# mk312lite_V4.net
KiCad netlist of a schematic drawn in EAGLE
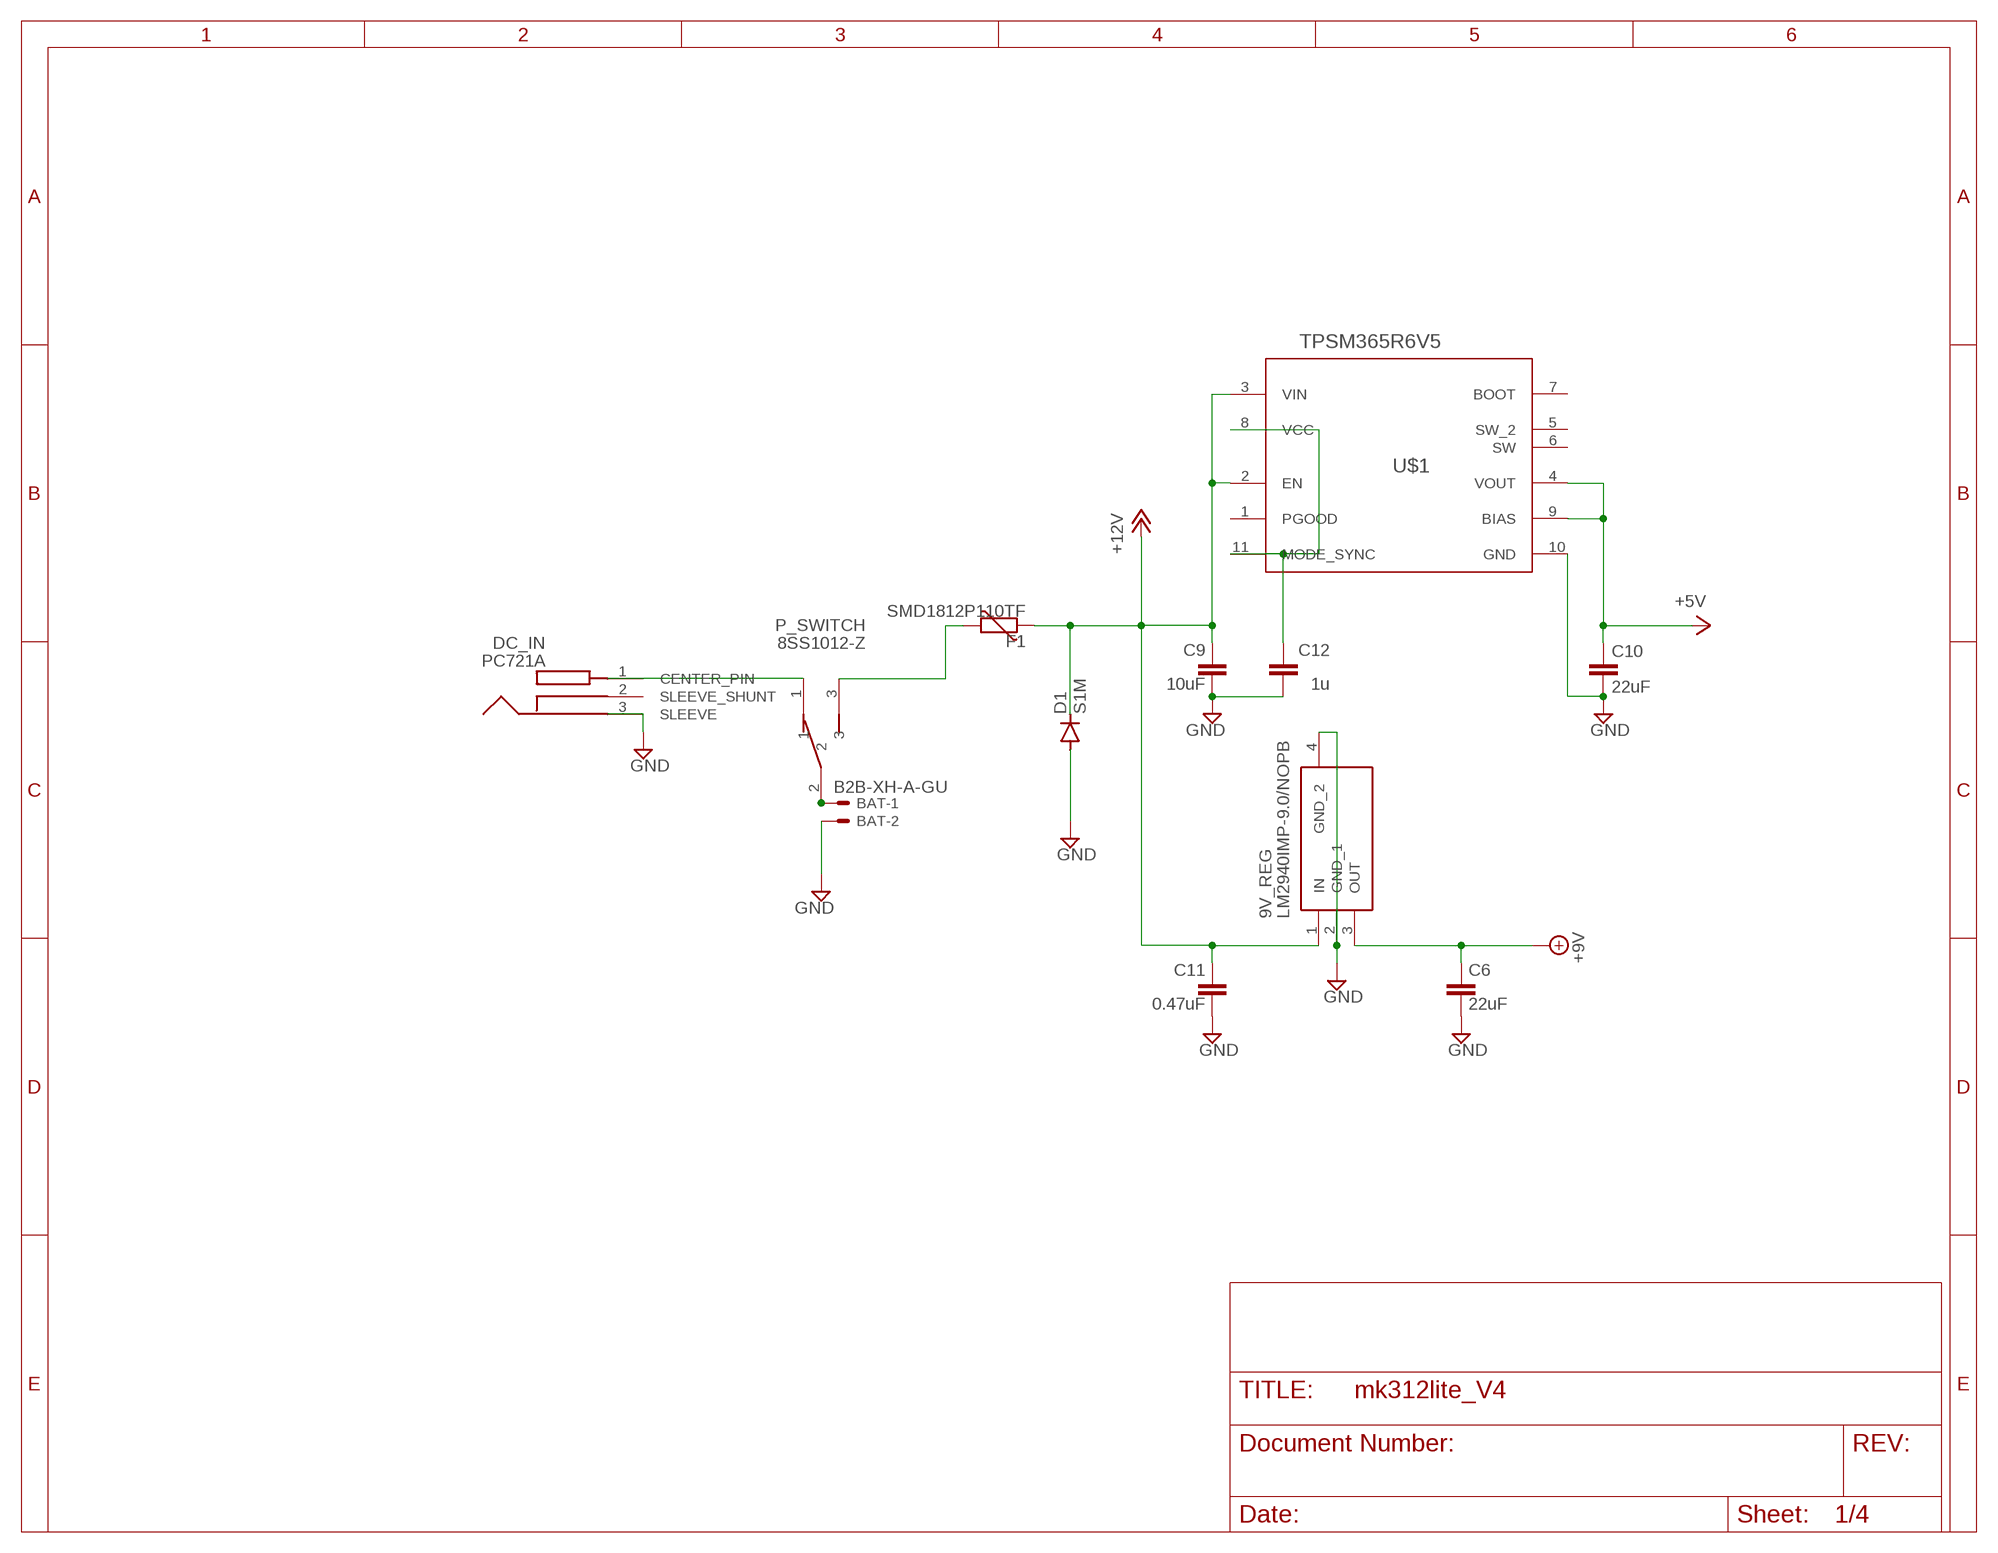
[diagram p0: schematic, sheet 1]
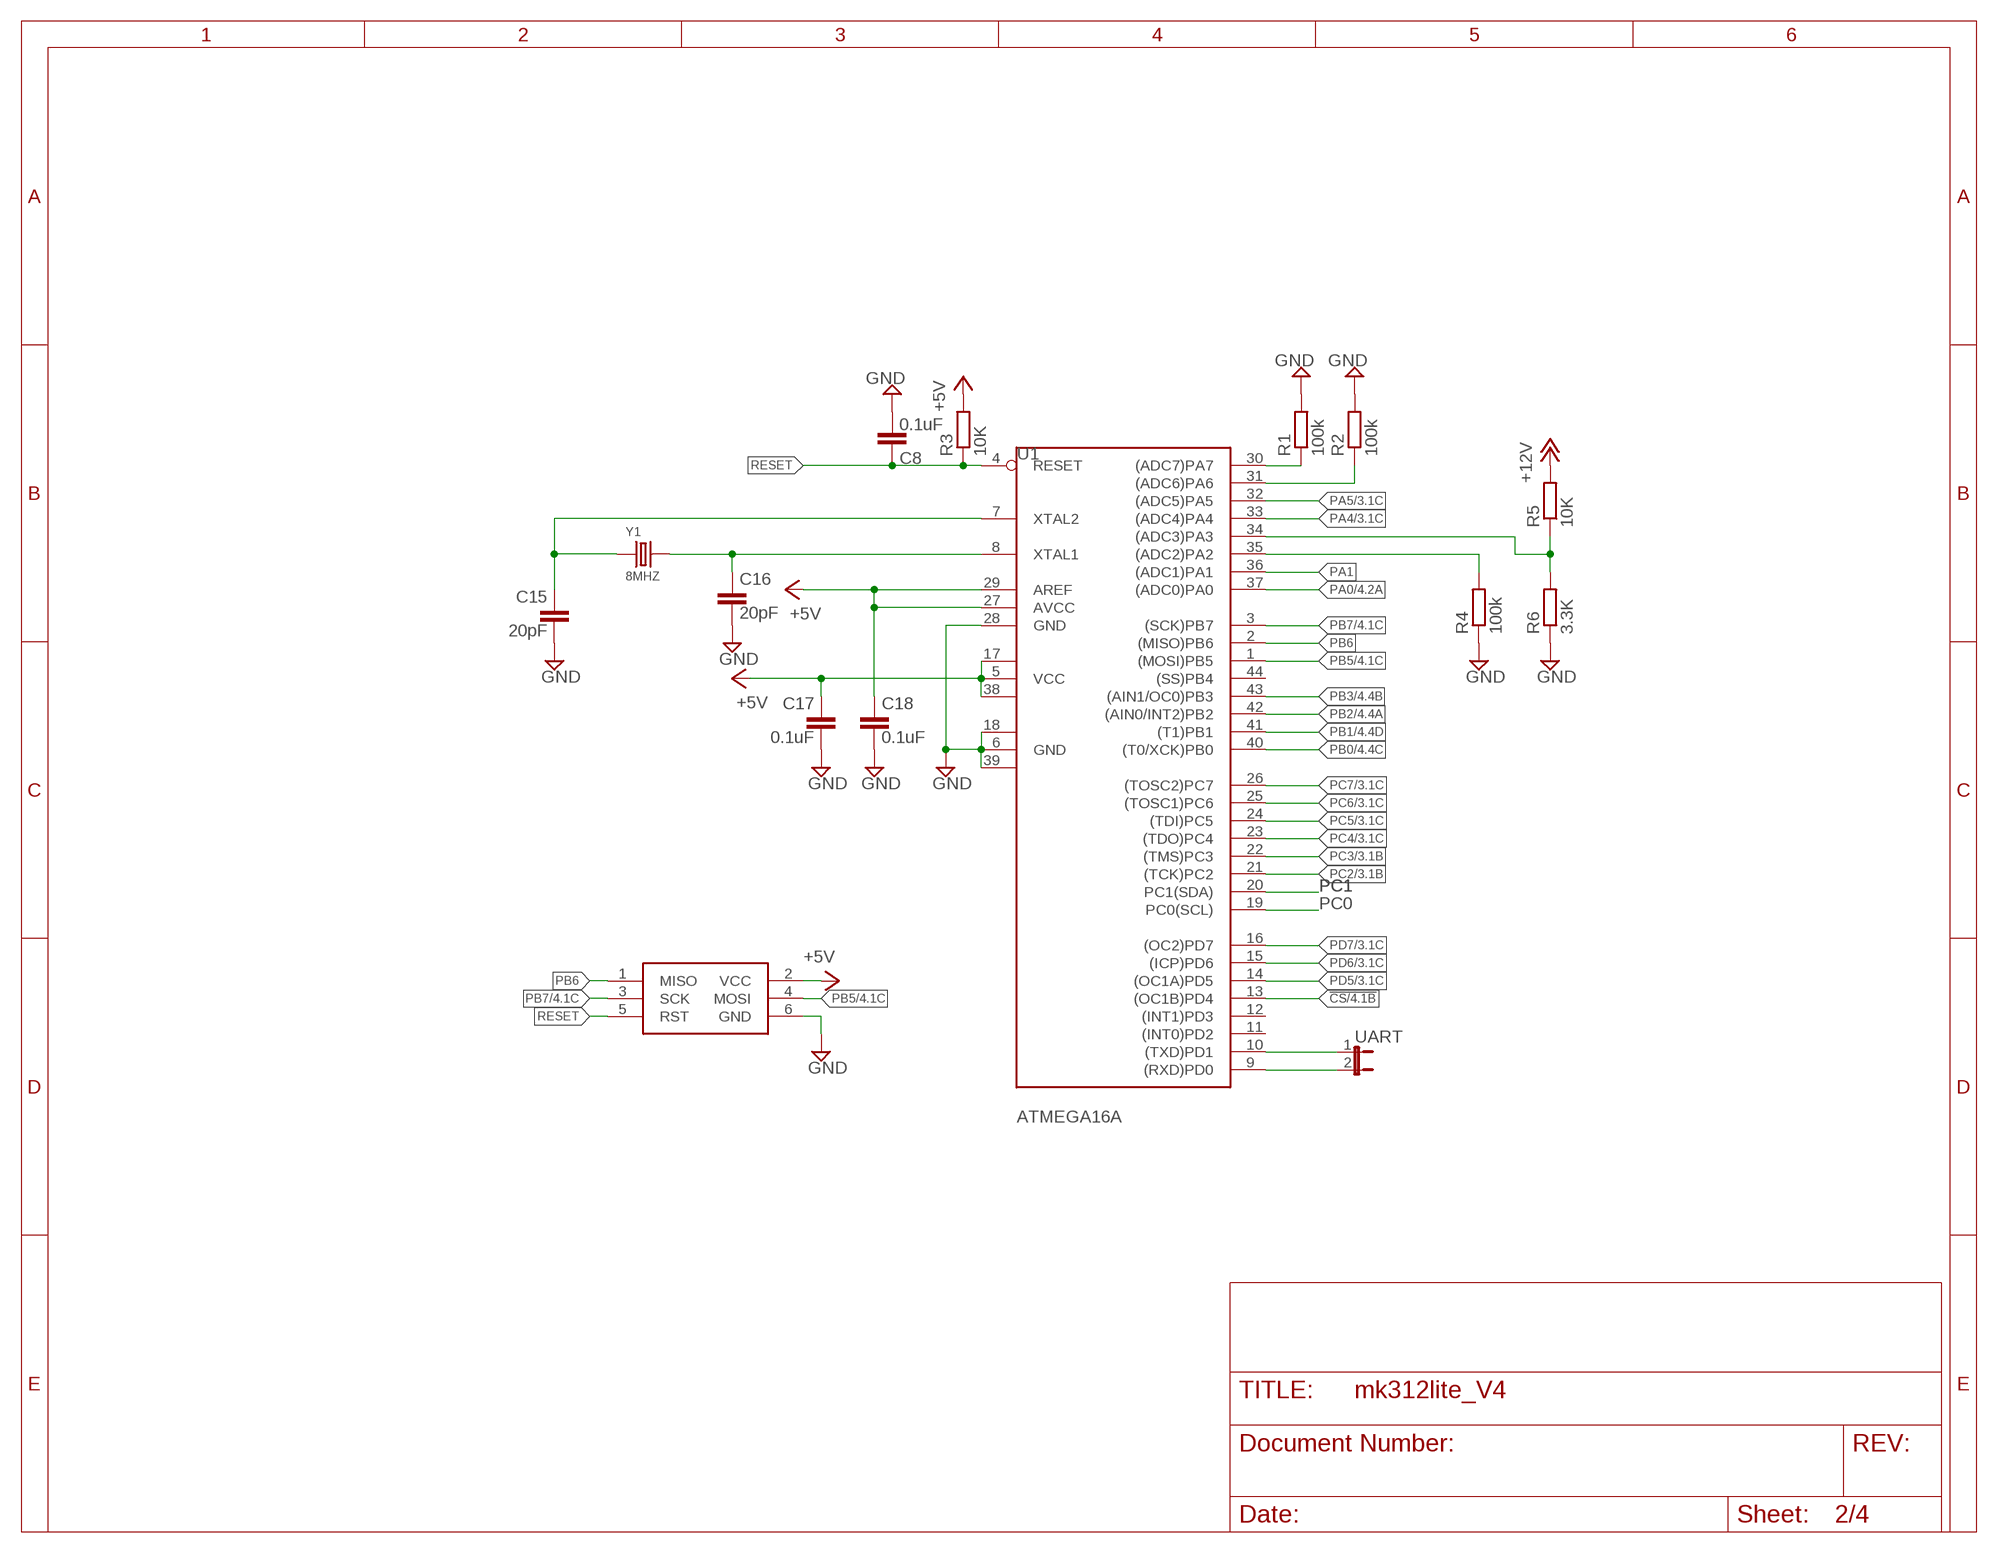
[diagram p1: schematic, sheet 2]
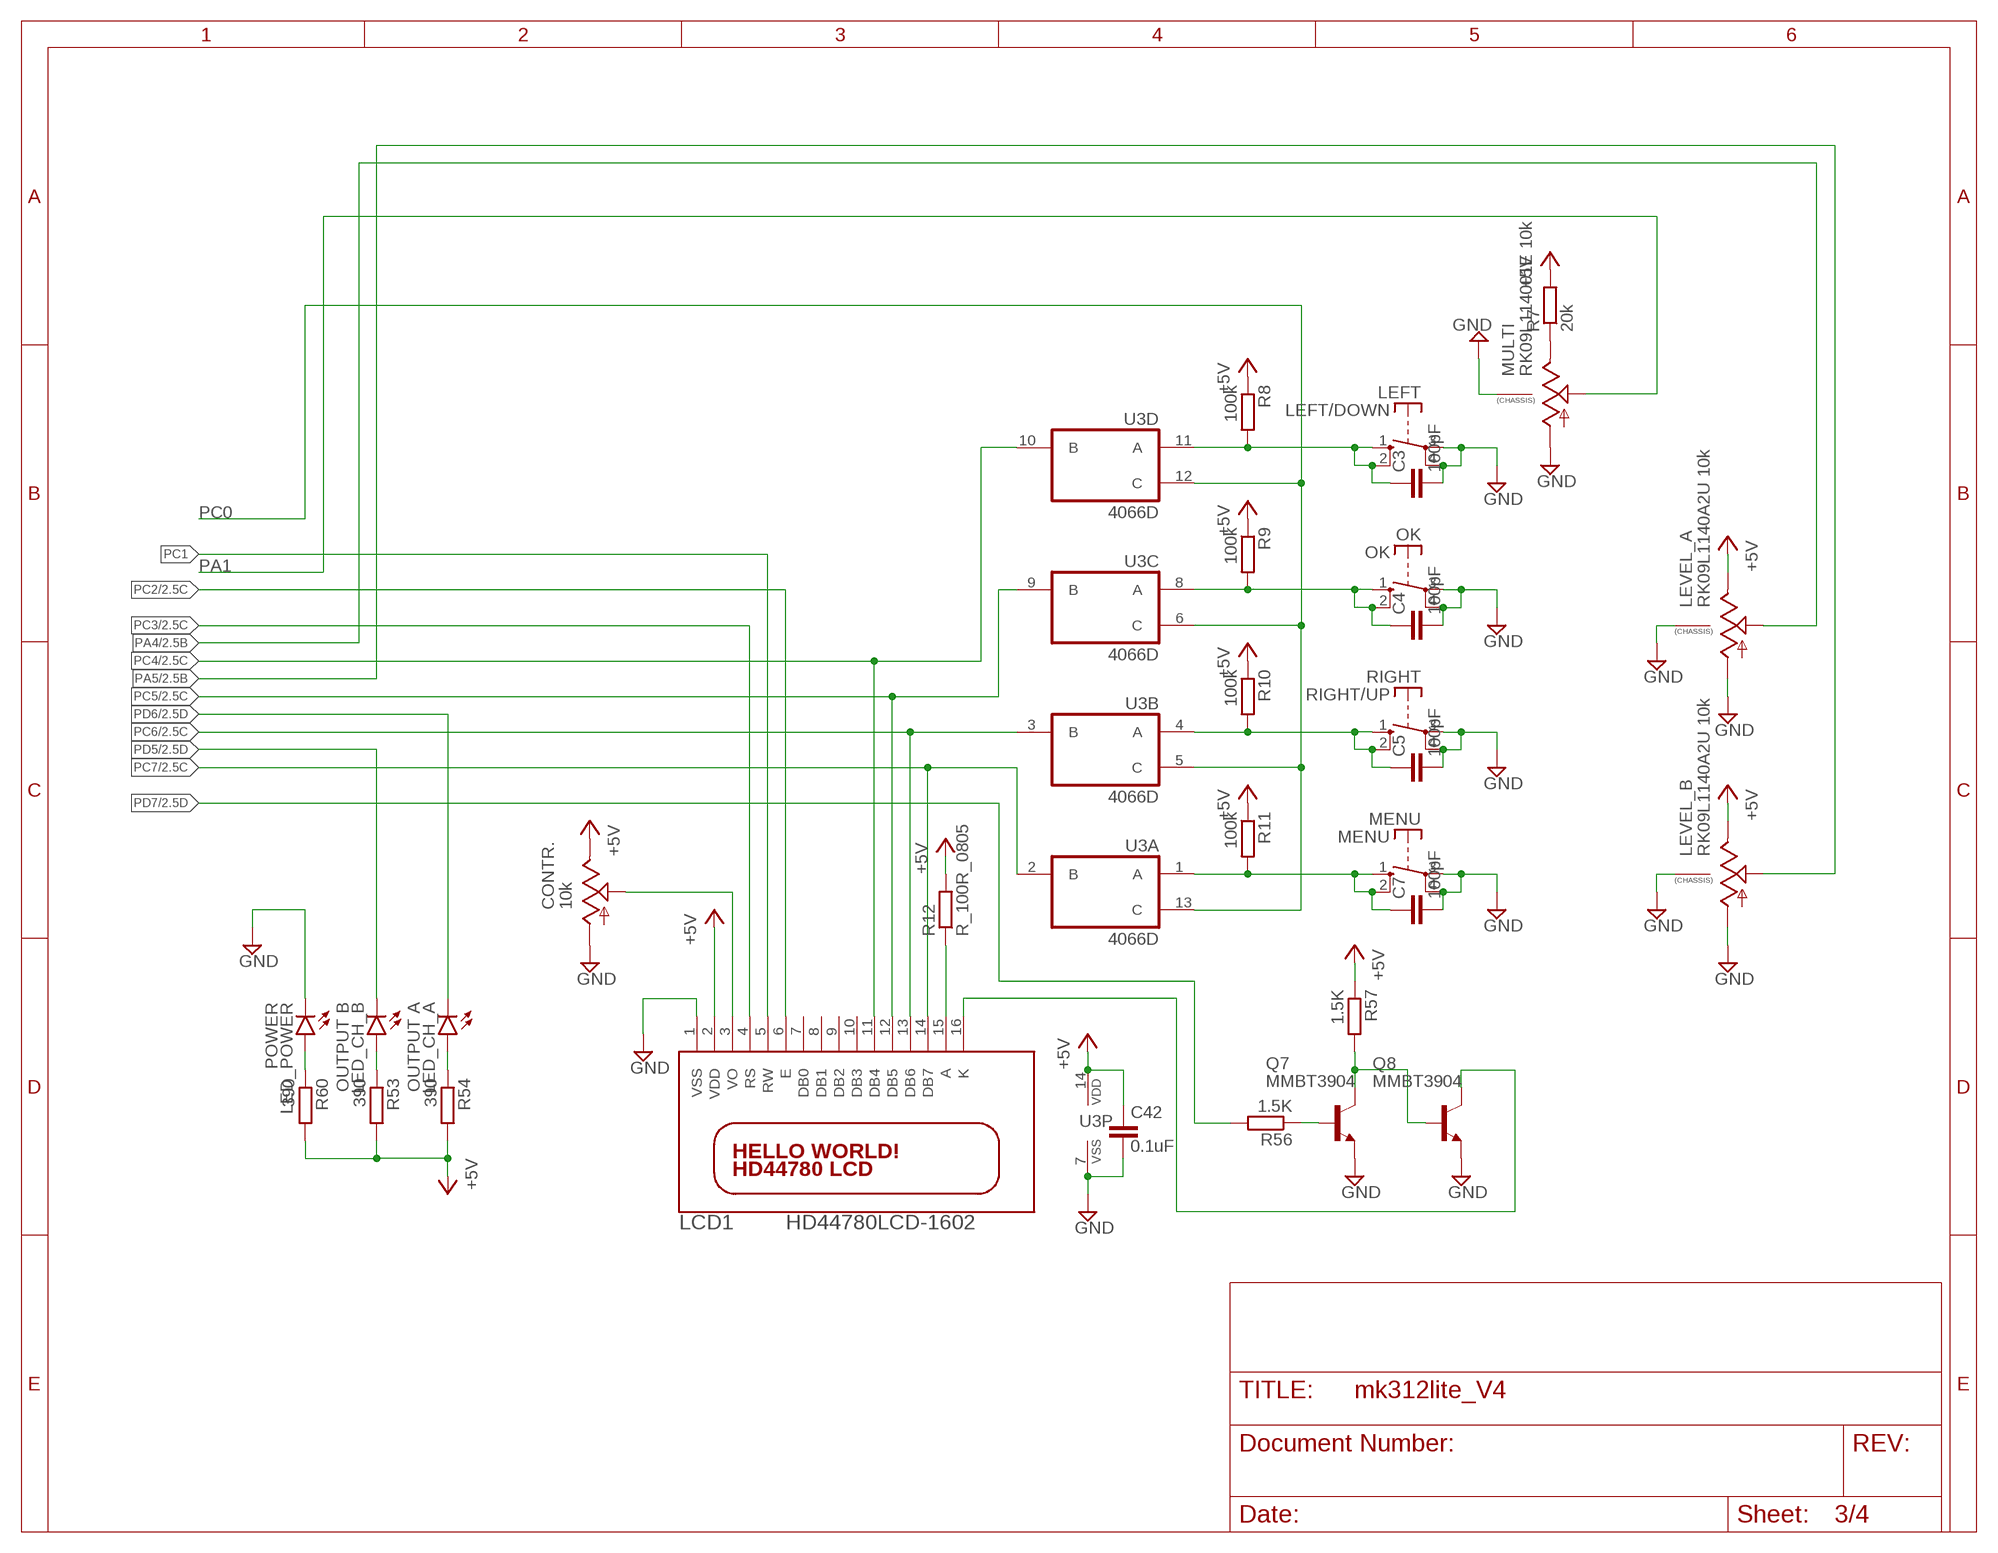
[diagram p2: schematic, sheet 3]
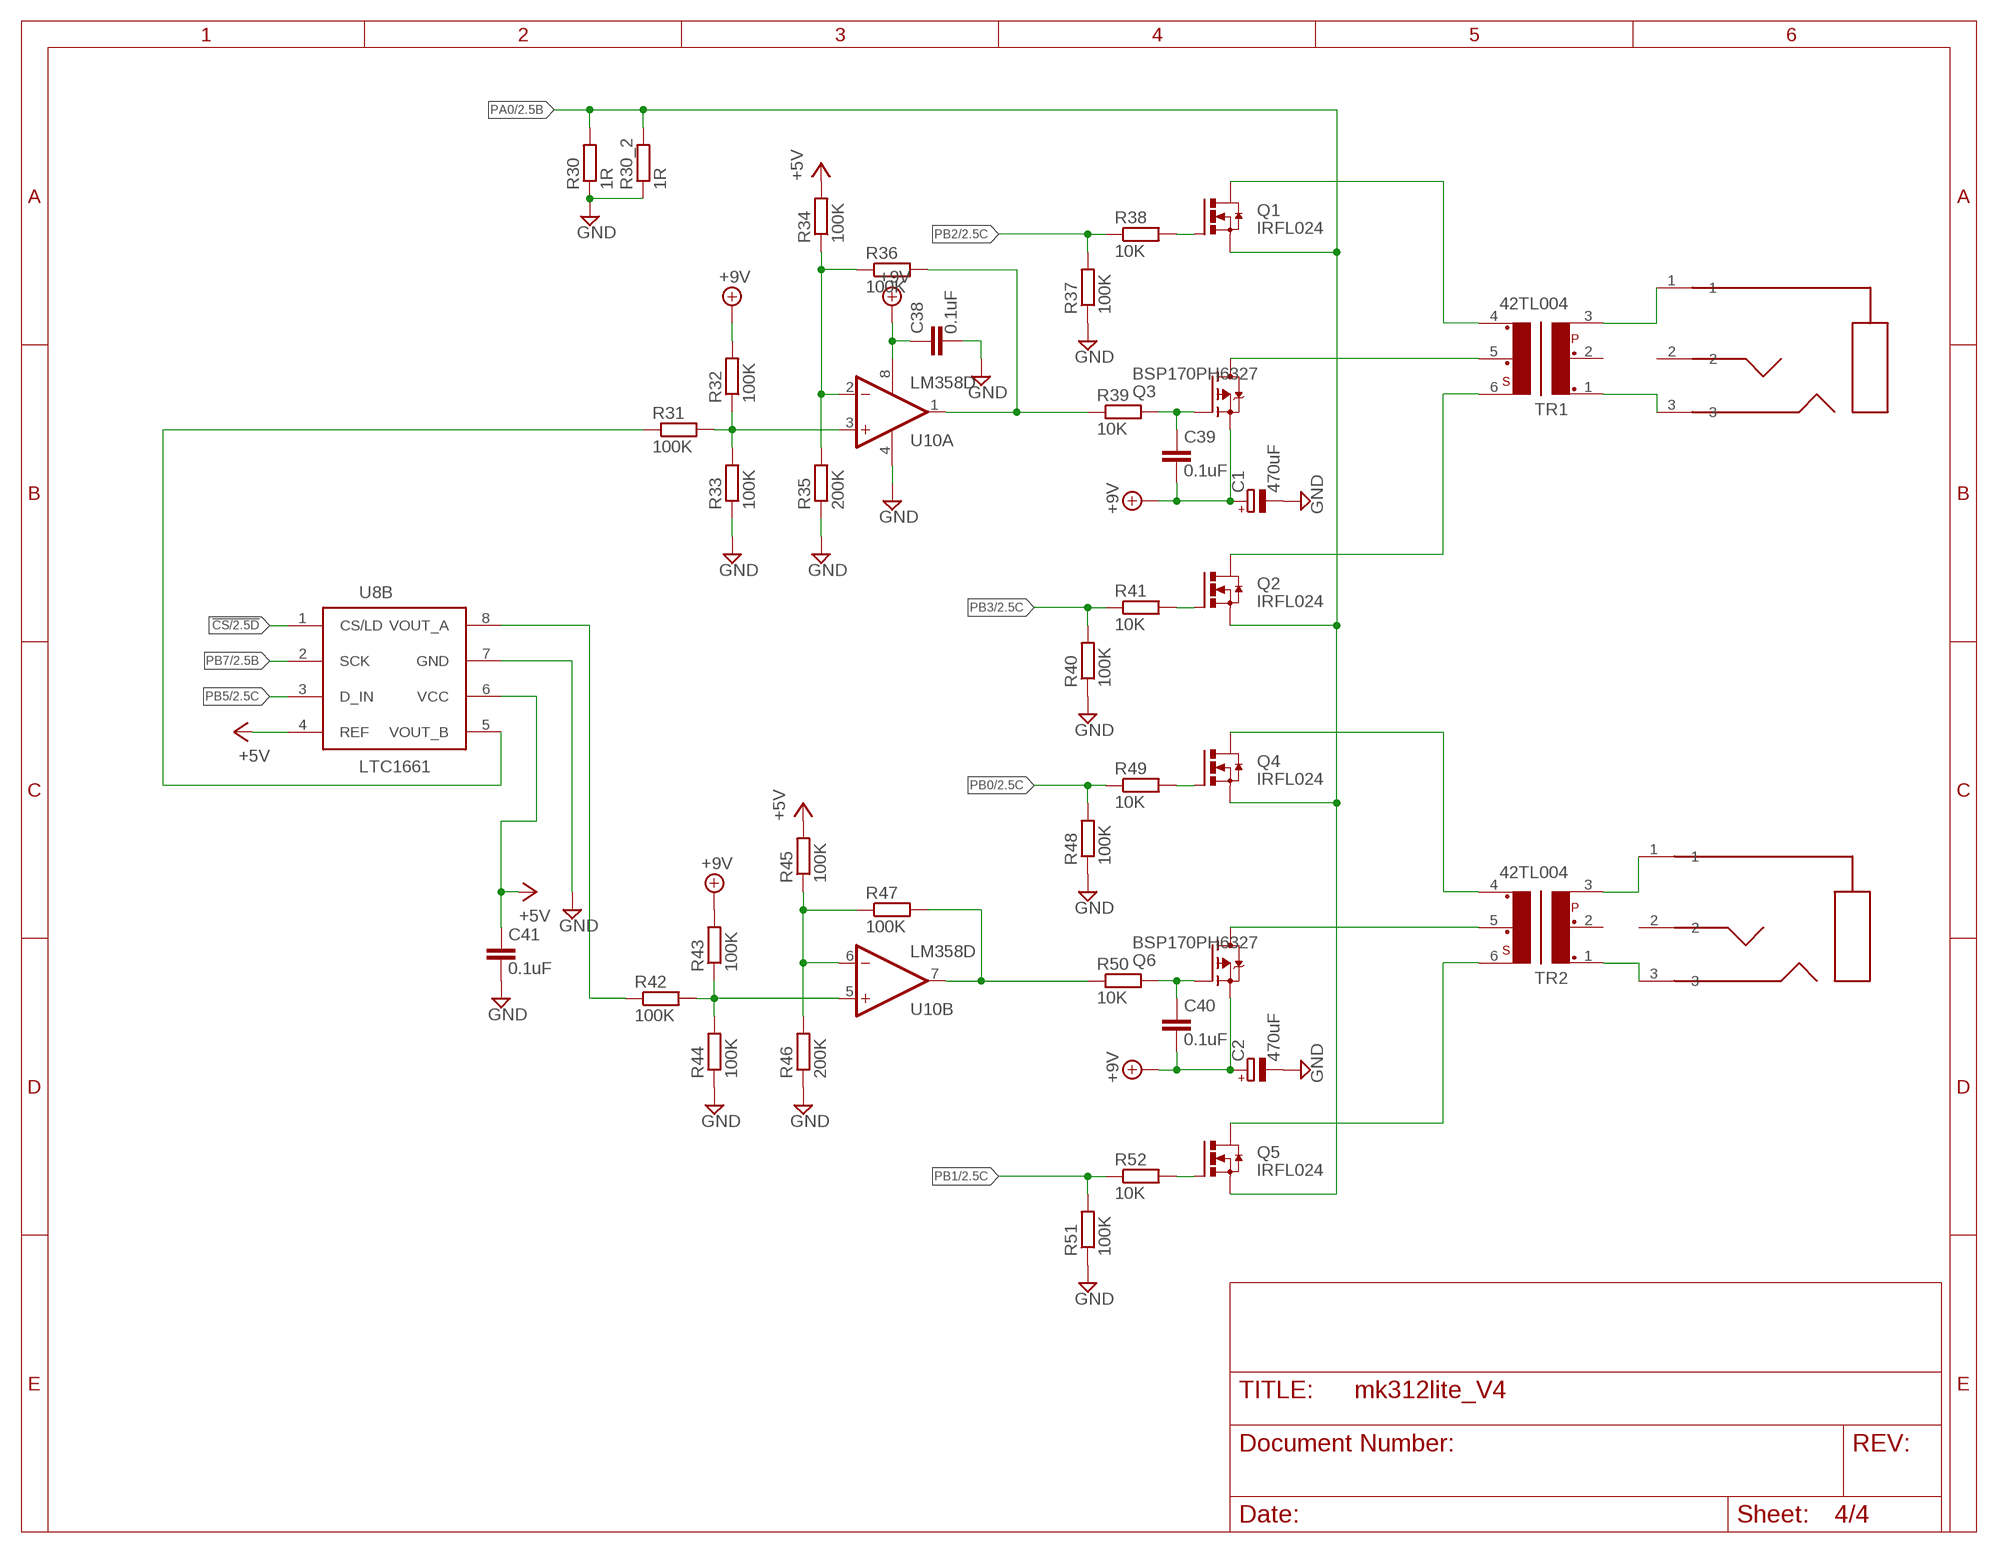
[diagram p3: schematic, sheet 4]

(export (version "E")
  (design (tool "Eeschema 10.0.6"))
  (components
    (comp (ref "C3")
      (value "100pF")
      (footprint "eagle-import:C0805")
      (libsource (lib "eagle-import") (part "C-EUC0805"))
    )
    (comp (ref "C4")
      (value "100pF")
      (footprint "eagle-import:C0805")
      (libsource (lib "eagle-import") (part "C-EUC0805"))
    )
    (comp (ref "C5")
      (value "100pF")
      (footprint "eagle-import:C0805")
      (libsource (lib "eagle-import") (part "C-EUC0805"))
    )
    (comp (ref "C7")
      (value "100pF")
      (footprint "eagle-import:C0805")
      (libsource (lib "eagle-import") (part "C-EUC0805"))
    )
    (comp (ref "C42")
      (value "0.1uF")
      (footprint "eagle-import:C0805")
      (libsource (lib "eagle-import") (part "C-EUC0805"))
    )
    (comp (ref "CONTR.")
      (value "10k")
      (footprint "eagle-import:B25P")
      (libsource (lib "eagle-import") (part "TRIM_US-B25P"))
    )
    (comp (ref "LCD1")
      (value "HD44780LCD-1602")
      (footprint "eagle-import:LCD1602")
      (libsource (lib "eagle-import") (part "HD44780LCD-1602"))
    )
    (comp (ref "LED_CH_A")
      (value "OUTPUT A")
      (footprint "eagle-import:LED3MM")
      (libsource (lib "eagle-import") (part "LED3MM"))
    )
    (comp (ref "LED_CH_B")
      (value "OUTPUT B")
      (footprint "eagle-import:LED3MM")
      (libsource (lib "eagle-import") (part "LED3MM"))
    )
    (comp (ref "LED_POWER")
      (value "POWER")
      (footprint "eagle-import:LED3MM")
      (libsource (lib "eagle-import") (part "LED3MM"))
    )
    (comp (ref "LEFT")
      (value "LEFT/DOWN")
      (footprint "eagle-import:DTE6K")
      (libsource (lib "eagle-import") (part "DTE6K"))
    )
    (comp (ref "LEVEL_A")
      (value "RK09L1140A2U 10k")
      (footprint "eagle-import:9MM_SNAP-IN_POT")
      (libsource (lib "eagle-import") (part "9MM_SNAP-IN_POT_CHASSIS"))
    )
    (comp (ref "LEVEL_B")
      (value "RK09L1140A2U 10k")
      (footprint "eagle-import:9MM_SNAP-IN_POT")
      (libsource (lib "eagle-import") (part "9MM_SNAP-IN_POT_CHASSIS"))
    )
    (comp (ref "MENU")
      (value "MENU")
      (footprint "eagle-import:DTE6K")
      (libsource (lib "eagle-import") (part "DTE6K"))
    )
    (comp (ref "MULTI")
      (value "RK09L114001E 10k")
      (footprint "eagle-import:9MM_SNAP-IN_POT")
      (libsource (lib "eagle-import") (part "9MM_SNAP-IN_POT_CHASSIS"))
    )
    (comp (ref "OK")
      (value "OK")
      (footprint "eagle-import:DTE6K")
      (libsource (lib "eagle-import") (part "DTE6K"))
    )
    (comp (ref "Q7")
      (value "MMBT3904")
      (footprint "eagle-import:SOT23-BEC")
      (libsource (lib "eagle-import") (part "-NPN-SOT23-BECMMBT3904LT1"))
    )
    (comp (ref "Q8")
      (value "MMBT3904")
      (footprint "eagle-import:SOT23-BEC")
      (libsource (lib "eagle-import") (part "-NPN-SOT23-BECMMBT3904LT1"))
    )
    (comp (ref "R7")
      (value "20k")
      (footprint "eagle-import:R0805")
      (libsource (lib "eagle-import") (part "R-EU_R0805"))
    )
    (comp (ref "R8")
      (value "100k")
      (footprint "eagle-import:R0805")
      (libsource (lib "eagle-import") (part "R-EU_R0805"))
    )
    (comp (ref "R9")
      (value "100k")
      (footprint "eagle-import:R0805")
      (libsource (lib "eagle-import") (part "R-EU_R0805"))
    )
    (comp (ref "R10")
      (value "100k")
      (footprint "eagle-import:R0805")
      (libsource (lib "eagle-import") (part "R-EU_R0805"))
    )
    (comp (ref "R11")
      (value "100k")
      (footprint "eagle-import:R0805")
      (libsource (lib "eagle-import") (part "R-EU_R0805"))
    )
    (comp (ref "R12")
      (value "R_100R_0805")
      (footprint "eagle-import:R0805")
      (fields (field (name "LCSC_PART") "C17408"))
      (libsource (lib "eagle-import") (part "R__0805100R"))
    )
    (comp (ref "R53")
      (value "390")
      (footprint "eagle-import:R0805")
      (libsource (lib "eagle-import") (part "R-EU_R0805"))
    )
    (comp (ref "R54")
      (value "390")
      (footprint "eagle-import:R0805")
      (libsource (lib "eagle-import") (part "R-EU_R0805"))
    )
    (comp (ref "R56")
      (value "1.5K")
      (footprint "eagle-import:R0805")
      (libsource (lib "eagle-import") (part "R-EU_R0805"))
    )
    (comp (ref "R57")
      (value "1.5K")
      (footprint "eagle-import:R0805")
      (libsource (lib "eagle-import") (part "R-EU_R0805"))
    )
    (comp (ref "R60")
      (value "390")
      (footprint "eagle-import:R0805")
      (libsource (lib "eagle-import") (part "R-EU_R0805"))
    )
    (comp (ref "RIGHT")
      (value "RIGHT/UP")
      (footprint "eagle-import:DTE6K")
      (libsource (lib "eagle-import") (part "DTE6K"))
    )
    (comp (ref "U3")
      (value "4066D")
      (footprint "eagle-import:SO14")
      (libsource (lib "eagle-import") (part "4066D"))
    )
    (comp (ref "C8")
      (value "0.1uF")
      (footprint "eagle-import:C0805")
      (libsource (lib "eagle-import") (part "C-EUC0805"))
    )
    (comp (ref "C15")
      (value "20pF")
      (footprint "eagle-import:C0603")
      (libsource (lib "eagle-import") (part "C-EUC0603"))
    )
    (comp (ref "C16")
      (value "20pF")
      (footprint "eagle-import:C0603")
      (libsource (lib "eagle-import") (part "C-EUC0603"))
    )
    (comp (ref "C17")
      (value "0.1uF")
      (footprint "eagle-import:C0805")
      (libsource (lib "eagle-import") (part "C-EUC0805"))
    )
    (comp (ref "C18")
      (value "0.1uF")
      (footprint "eagle-import:C0805")
      (libsource (lib "eagle-import") (part "C-EUC0805"))
    )
    (comp (ref "ISP1")
      (value "AVRISP-6")
      (footprint "eagle-import:AVRISP")
      (libsource (lib "eagle-import") (part "AVRISP-6"))
    )
    (comp (ref "R1")
      (value "100k")
      (footprint "eagle-import:R0805")
      (libsource (lib "eagle-import") (part "R-EU_R0805"))
    )
    (comp (ref "R2")
      (value "100k")
      (footprint "eagle-import:R0805")
      (libsource (lib "eagle-import") (part "R-EU_R0805"))
    )
    (comp (ref "R3")
      (value "10K")
      (footprint "eagle-import:R0805")
      (libsource (lib "eagle-import") (part "R-EU_R0805"))
    )
    (comp (ref "R4")
      (value "100k")
      (footprint "eagle-import:R0805")
      (libsource (lib "eagle-import") (part "R-EU_R0805"))
    )
    (comp (ref "R5")
      (value "10K")
      (footprint "eagle-import:R0805")
      (libsource (lib "eagle-import") (part "R-EU_R0805"))
    )
    (comp (ref "R6")
      (value "3.3K")
      (footprint "eagle-import:R0805")
      (libsource (lib "eagle-import") (part "R-EU_R0805"))
    )
    (comp (ref "U1")
      (value "ATMEGA16A")
      (footprint "eagle-import:TQFP44")
      (fields (field (name "MPN") "ATMEGA16-16AU"))
      (libsource (lib "eagle-import") (part "MEGA16-A"))
    )
    (comp (ref "UART")
      (value "JP1E")
      (footprint "eagle-import:JP1")
      (libsource (lib "eagle-import") (part "JP1E"))
    )
    (comp (ref "Y1")
      (value "8MHZ")
      (footprint "eagle-import:X2-SMD-5.0X3.2X1.3MM")
      (fields (field (name "MPN") "5032/2P"))
      (libsource (lib "eagle-import") (part "SMD-CRYSTAL-8MHZ-20PF-20PPM(2P-5.0X3.2MM)"))
    )
    (comp (ref "C1")
      (value "470uF")
      (footprint "eagle-import:150CLZ-1010")
      (libsource (lib "eagle-import") (part "CPOL-EU150CLZ-1010"))
    )
    (comp (ref "C2")
      (value "470uF")
      (footprint "eagle-import:150CLZ-1010")
      (libsource (lib "eagle-import") (part "CPOL-EU150CLZ-1010"))
    )
    (comp (ref "C38")
      (value "0.1uF")
      (footprint "eagle-import:C0805")
      (libsource (lib "eagle-import") (part "C-EUC0805"))
    )
    (comp (ref "C39")
      (value "0.1uF")
      (footprint "eagle-import:C0805")
      (libsource (lib "eagle-import") (part "C-EUC0805"))
    )
    (comp (ref "C40")
      (value "0.1uF")
      (footprint "eagle-import:C0805")
      (libsource (lib "eagle-import") (part "C-EUC0805"))
    )
    (comp (ref "C41")
      (value "0.1uF")
      (footprint "eagle-import:C0805")
      (libsource (lib "eagle-import") (part "C-EUC0805"))
    )
    (comp (ref "CHAN_A")
      (value "PJ-301C")
      (footprint "eagle-import:PJ-301C")
      (libsource (lib "eagle-import") (part "PC-301C"))
    )
    (comp (ref "CHAN_B")
      (value "PJ-301C")
      (footprint "eagle-import:PJ-301C")
      (libsource (lib "eagle-import") (part "PC-301C"))
    )
    (comp (ref "Q1")
      (value "IRFL024")
      (footprint "eagle-import:SOT223")
      (libsource (lib "eagle-import") (part "N-HEXFET-2D_?-SOT232IRLL2705"))
    )
    (comp (ref "Q2")
      (value "IRFL024")
      (footprint "eagle-import:SOT223")
      (libsource (lib "eagle-import") (part "N-HEXFET-2D_?-SOT232IRLL2705"))
    )
    (comp (ref "Q3")
      (value "BSP170PH6327")
      (footprint "eagle-import:SOT230P700X180-4N")
      (libsource (lib "eagle-import") (part "IRFL9014TRPBF"))
    )
    (comp (ref "Q4")
      (value "IRFL024")
      (footprint "eagle-import:SOT223")
      (libsource (lib "eagle-import") (part "N-HEXFET-2D_?-SOT232IRLL2705"))
    )
    (comp (ref "Q5")
      (value "IRFL024")
      (footprint "eagle-import:SOT223")
      (libsource (lib "eagle-import") (part "N-HEXFET-2D_?-SOT232IRLL2705"))
    )
    (comp (ref "Q6")
      (value "BSP170PH6327")
      (footprint "eagle-import:SOT230P700X180-4N")
      (libsource (lib "eagle-import") (part "IRFL9014TRPBF"))
    )
    (comp (ref "R30")
      (value "1R")
      (footprint "eagle-import:R1206")
      (libsource (lib "eagle-import") (part "R-EU_R1206"))
    )
    (comp (ref "R30_2")
      (value "1R")
      (footprint "eagle-import:R1206")
      (libsource (lib "eagle-import") (part "R-EU_R1206"))
    )
    (comp (ref "R31")
      (value "100K")
      (footprint "eagle-import:R0805")
      (libsource (lib "eagle-import") (part "R-EU_R0805"))
    )
    (comp (ref "R32")
      (value "100K")
      (footprint "eagle-import:R0805")
      (libsource (lib "eagle-import") (part "R-EU_R0805"))
    )
    (comp (ref "R33")
      (value "100K")
      (footprint "eagle-import:R0805")
      (libsource (lib "eagle-import") (part "R-EU_R0805"))
    )
    (comp (ref "R34")
      (value "100K")
      (footprint "eagle-import:R0805")
      (libsource (lib "eagle-import") (part "R-EU_R0805"))
    )
    (comp (ref "R35")
      (value "200K")
      (footprint "eagle-import:R0805")
      (libsource (lib "eagle-import") (part "R-EU_R0805"))
    )
    (comp (ref "R36")
      (value "100K")
      (footprint "eagle-import:R0805")
      (libsource (lib "eagle-import") (part "R-EU_R0805"))
    )
    (comp (ref "R37")
      (value "100K")
      (footprint "eagle-import:R0805")
      (libsource (lib "eagle-import") (part "R-EU_R0805"))
    )
    (comp (ref "R38")
      (value "10K")
      (footprint "eagle-import:R0805")
      (libsource (lib "eagle-import") (part "R-EU_R0805"))
    )
    (comp (ref "R39")
      (value "10K")
      (footprint "eagle-import:R0805")
      (libsource (lib "eagle-import") (part "R-EU_R0805"))
    )
    (comp (ref "R40")
      (value "100K")
      (footprint "eagle-import:R0805")
      (libsource (lib "eagle-import") (part "R-EU_R0805"))
    )
    (comp (ref "R41")
      (value "10K")
      (footprint "eagle-import:R0805")
      (libsource (lib "eagle-import") (part "R-EU_R0805"))
    )
    (comp (ref "R42")
      (value "100K")
      (footprint "eagle-import:R0805")
      (libsource (lib "eagle-import") (part "R-EU_R0805"))
    )
    (comp (ref "R43")
      (value "100K")
      (footprint "eagle-import:R0805")
      (libsource (lib "eagle-import") (part "R-EU_R0805"))
    )
    (comp (ref "R44")
      (value "100K")
      (footprint "eagle-import:R0805")
      (libsource (lib "eagle-import") (part "R-EU_R0805"))
    )
    (comp (ref "R45")
      (value "100K")
      (footprint "eagle-import:R0805")
      (libsource (lib "eagle-import") (part "R-EU_R0805"))
    )
    (comp (ref "R46")
      (value "200K")
      (footprint "eagle-import:R0805")
      (libsource (lib "eagle-import") (part "R-EU_R0805"))
    )
    (comp (ref "R47")
      (value "100K")
      (footprint "eagle-import:R0805")
      (libsource (lib "eagle-import") (part "R-EU_R0805"))
    )
    (comp (ref "R48")
      (value "100K")
      (footprint "eagle-import:R0805")
      (libsource (lib "eagle-import") (part "R-EU_R0805"))
    )
    (comp (ref "R49")
      (value "10K")
      (footprint "eagle-import:R0805")
      (libsource (lib "eagle-import") (part "R-EU_R0805"))
    )
    (comp (ref "R50")
      (value "10K")
      (footprint "eagle-import:R0805")
      (libsource (lib "eagle-import") (part "R-EU_R0805"))
    )
    (comp (ref "R51")
      (value "100K")
      (footprint "eagle-import:R0805")
      (libsource (lib "eagle-import") (part "R-EU_R0805"))
    )
    (comp (ref "R52")
      (value "10K")
      (footprint "eagle-import:R0805")
      (libsource (lib "eagle-import") (part "R-EU_R0805"))
    )
    (comp (ref "TR1")
      (value "42TL004")
      (footprint "eagle-import:42TL")
      (libsource (lib "eagle-import") (part "42T?L023"))
    )
    (comp (ref "TR2")
      (value "42TL004")
      (footprint "eagle-import:42TL")
      (libsource (lib "eagle-import") (part "42T?L023"))
    )
    (comp (ref "U8B")
      (value "LTC1661")
      (footprint "eagle-import:MSOP8")
      (libsource (lib "eagle-import") (part "LTC1661IMS8"))
    )
    (comp (ref "U10")
      (value "LM358D")
      (footprint "eagle-import:SO08")
      (libsource (lib "eagle-import") (part "LM358D"))
    )
    (comp (ref "9V_REG")
      (value "LM2940IMP-9.0/NOPB")
      (footprint "eagle-import:SOT230P700X180-4N")
      (fields (field (name "MOUSER_PART_NUMBER") "926-LM2940IMP90NOPB"))
      (libsource (lib "eagle-import") (part "LM2940IMP-9.0_NOPB"))
    )
    (comp (ref "BAT")
      (value "B2B-XH-A-GU")
      (footprint "eagle-import:JST-XH-02-PACKAGE-LONG-PAD")
      (libsource (lib "eagle-import") (part "JST-XH-02-PIN-LONG-PAD"))
    )
    (comp (ref "C6")
      (value "22uF")
      (footprint "eagle-import:C1206")
      (libsource (lib "eagle-import") (part "C-EUC1206"))
    )
    (comp (ref "C9")
      (value "10uF")
      (footprint "eagle-import:C0805")
      (libsource (lib "eagle-import") (part "C-EUC0805"))
    )
    (comp (ref "C10")
      (value "22uF")
      (footprint "eagle-import:C1206")
      (libsource (lib "eagle-import") (part "C-EUC1206"))
    )
    (comp (ref "C11")
      (value "0.47uF")
      (footprint "eagle-import:C0805")
      (libsource (lib "eagle-import") (part "C-EUC0805"))
    )
    (comp (ref "C12")
      (value "1u")
      (footprint "eagle-import:C0805")
      (libsource (lib "eagle-import") (part "C-EUC0805"))
    )
    (comp (ref "D1")
      (value "S1M")
      (footprint "eagle-import:SMA")
      (libsource (lib "eagle-import") (part "S1M"))
    )
    (comp (ref "DC_IN")
      (value "PC721A")
      (footprint "eagle-import:PC721A")
      (fields (field (name "MOUSER_PART_NUMBER") "502-PC721A"))
      (libsource (lib "eagle-import") (part "PC721A"))
    )
    (comp (ref "F1")
      (value "SMD1812P110TF")
      (footprint "eagle-import:CT_CN1812")
      (libsource (lib "eagle-import") (part "VARISTORCN1812"))
    )
    (comp (ref "P_SWITCH")
      (value "8SS1012-Z")
      (footprint "eagle-import:8SS1012Z")
      (libsource (lib "eagle-import") (part "8SS1012-Z"))
    )
    (comp (ref "U$1")
      (value "TPSM365R6V5")
      (footprint "eagle-import:RDN0011A-MFG")
      (fields
        (field (name "MANUFACTURER_PART_NUMBER") "PTPSM365R6FRDN")
        (field (name "COPYRIGHT") "Copyright (C) 2025 Ultra Librarian. All rights reserved.")
      )
      (libsource (lib "eagle-import") (part "PTPSM365R6FRDN"))
    )
  )
  (nets
    (net (code "1") (name "+5V") (class "Default")
      (node (ref "C10") (pin "1") (pinfunction "1_1") (pintype "passive"))
      (node (ref "C17") (pin "1") (pinfunction "1_1") (pintype "passive"))
      (node (ref "C18") (pin "1") (pinfunction "1_1") (pintype "passive"))
      (node (ref "C41") (pin "1") (pinfunction "1_1") (pintype "passive"))
      (node (ref "C42") (pin "1") (pinfunction "1_1") (pintype "passive"))
      (node (ref "CONTR.") (pin "E") (pinfunction "E_E") (pintype "passive"))
      (node (ref "ISP1") (pin "2") (pinfunction "VCC_2") (pintype "power_in"))
      (node (ref "LCD1") (pin "2") (pinfunction "VDD_2") (pintype "power_in"))
      (node (ref "LEVEL_A") (pin "3") (pinfunction "E_3") (pintype "passive"))
      (node (ref "LEVEL_B") (pin "3") (pinfunction "E_3") (pintype "passive"))
      (node (ref "R10") (pin "1") (pinfunction "1_1") (pintype "passive"))
      (node (ref "R11") (pin "1") (pinfunction "1_1") (pintype "passive"))
      (node (ref "R12") (pin "2") (pinfunction "2_2") (pintype "passive"))
      (node (ref "R3") (pin "2") (pinfunction "2_2") (pintype "passive"))
      (node (ref "R34") (pin "2") (pinfunction "2_2") (pintype "passive"))
      (node (ref "R45") (pin "2") (pinfunction "2_2") (pintype "passive"))
      (node (ref "R53") (pin "2") (pinfunction "2_2") (pintype "passive"))
      (node (ref "R54") (pin "2") (pinfunction "2_2") (pintype "passive"))
      (node (ref "R57") (pin "1") (pinfunction "1_1") (pintype "passive"))
      (node (ref "R60") (pin "2") (pinfunction "2_2") (pintype "passive"))
      (node (ref "R7") (pin "2") (pinfunction "2_2") (pintype "passive"))
      (node (ref "R8") (pin "1") (pinfunction "1_1") (pintype "passive"))
      (node (ref "R9") (pin "1") (pinfunction "1_1") (pintype "passive"))
      (node (ref "U$1") (pin "4") (pinfunction "VOUT_4") (pintype "passive"))
      (node (ref "U$1") (pin "9") (pinfunction "BIAS_9") (pintype "passive"))
      (node (ref "U1") (pin "17") (pinfunction "VCC1_17") (pintype "power_in"))
      (node (ref "U1") (pin "27") (pinfunction "AVCC_27") (pintype "power_in"))
      (node (ref "U1") (pin "29") (pinfunction "AREF_29") (pintype "passive"))
      (node (ref "U1") (pin "38") (pinfunction "VCC2_38") (pintype "power_in"))
      (node (ref "U1") (pin "5") (pinfunction "VCC_5") (pintype "power_in"))
      (node (ref "U3") (pin "14") (pinfunction "VDD_14") (pintype "power_in"))
      (node (ref "U8B") (pin "4") (pinfunction "REF_4") (pintype "input"))
      (node (ref "U8B") (pin "6") (pinfunction "VCC_6") (pintype "power_in"))
    )
    (net (code "2") (name "+9V") (class "Default")
      (node (ref "9V_REG") (pin "3") (pinfunction "OUT_3") (pintype "bidirectional"))
      (node (ref "C1") (pin "+") (pinfunction "+_+") (pintype "passive"))
      (node (ref "C2") (pin "+") (pinfunction "+_+") (pintype "passive"))
      (node (ref "C38") (pin "1") (pinfunction "1_1") (pintype "passive"))
      (node (ref "C39") (pin "2") (pinfunction "2_2") (pintype "passive"))
      (node (ref "C40") (pin "2") (pinfunction "2_2") (pintype "passive"))
      (node (ref "C6") (pin "1") (pinfunction "1_1") (pintype "passive"))
      (node (ref "Q3") (pin "3") (pinfunction "S_3") (pintype "passive"))
      (node (ref "Q6") (pin "3") (pinfunction "S_3") (pintype "passive"))
      (node (ref "R32") (pin "2") (pinfunction "2_2") (pintype "passive"))
      (node (ref "R43") (pin "2") (pinfunction "2_2") (pintype "passive"))
      (node (ref "U10") (pin "8") (pinfunction "V+_8") (pintype "power_in"))
    )
    (net (code "3") (name "+12V") (class "Default")
      (node (ref "9V_REG") (pin "1") (pinfunction "IN_1") (pintype "bidirectional"))
      (node (ref "C11") (pin "1") (pinfunction "1_1") (pintype "passive"))
      (node (ref "C9") (pin "1") (pinfunction "1_1") (pintype "passive"))
      (node (ref "D1") (pin "C") (pinfunction "C_C") (pintype "passive"))
      (node (ref "F1") (pin "2") (pinfunction "2_2") (pintype "passive"))
      (node (ref "R5") (pin "2") (pinfunction "2_2") (pintype "passive"))
      (node (ref "U$1") (pin "2") (pinfunction "EN_2") (pintype "input"))
      (node (ref "U$1") (pin "3") (pinfunction "VIN_3") (pintype "power_in"))
    )
    (net (code "4") (name "GND") (class "Default")
      (node (ref "9V_REG") (pin "2") (pinfunction "GND_1_2") (pintype "bidirectional"))
      (node (ref "9V_REG") (pin "4") (pinfunction "GND_2_4") (pintype "bidirectional"))
      (node (ref "BAT") (pin "2") (pinfunction "S_2") (pintype "passive"))
      (node (ref "C1") (pin "-") (pinfunction "-_-") (pintype "passive"))
      (node (ref "C10") (pin "2") (pinfunction "2_2") (pintype "passive"))
      (node (ref "C11") (pin "2") (pinfunction "2_2") (pintype "passive"))
      (node (ref "C12") (pin "2") (pinfunction "2_2") (pintype "passive"))
      (node (ref "C15") (pin "2") (pinfunction "2_2") (pintype "passive"))
      (node (ref "C16") (pin "2") (pinfunction "2_2") (pintype "passive"))
      (node (ref "C17") (pin "2") (pinfunction "2_2") (pintype "passive"))
      (node (ref "C18") (pin "2") (pinfunction "2_2") (pintype "passive"))
      (node (ref "C2") (pin "-") (pinfunction "-_-") (pintype "passive"))
      (node (ref "C3") (pin "2") (pinfunction "2_2") (pintype "passive"))
      (node (ref "C38") (pin "2") (pinfunction "2_2") (pintype "passive"))
      (node (ref "C4") (pin "2") (pinfunction "2_2") (pintype "passive"))
      (node (ref "C41") (pin "2") (pinfunction "2_2") (pintype "passive"))
      (node (ref "C42") (pin "2") (pinfunction "2_2") (pintype "passive"))
      (node (ref "C5") (pin "2") (pinfunction "2_2") (pintype "passive"))
      (node (ref "C6") (pin "2") (pinfunction "2_2") (pintype "passive"))
      (node (ref "C7") (pin "2") (pinfunction "2_2") (pintype "passive"))
      (node (ref "C8") (pin "2") (pinfunction "2_2") (pintype "passive"))
      (node (ref "C9") (pin "2") (pinfunction "2_2") (pintype "passive"))
      (node (ref "CONTR.") (pin "A") (pinfunction "A_A") (pintype "passive"))
      (node (ref "D1") (pin "A") (pinfunction "A_A") (pintype "passive"))
      (node (ref "DC_IN") (pin "3") (pinfunction "SLEEVE_3") (pintype "bidirectional"))
      (node (ref "ISP1") (pin "6") (pinfunction "GND_6") (pintype "power_in"))
      (node (ref "LCD1") (pin "1") (pinfunction "VSS_1") (pintype "power_in"))
      (node (ref "LED_POWER") (pin "K") (pinfunction "C_K") (pintype "passive"))
      (node (ref "LEFT") (pin "3") (pinfunction "P_3") (pintype "passive"))
      (node (ref "LEFT") (pin "4") (pinfunction "P_4") (pintype "passive"))
      (node (ref "LEVEL_A") (pin "1") (pinfunction "A_1") (pintype "passive"))
      (node (ref "LEVEL_A") (pin "CHASSIS2") (pinfunction "P$1_CHASSIS2") (pintype "passive"))
      (node (ref "LEVEL_B") (pin "1") (pinfunction "A_1") (pintype "passive"))
      (node (ref "LEVEL_B") (pin "CHASSIS2") (pinfunction "P$1_CHASSIS2") (pintype "passive"))
      (node (ref "MENU") (pin "3") (pinfunction "P_3") (pintype "passive"))
      (node (ref "MENU") (pin "4") (pinfunction "P_4") (pintype "passive"))
      (node (ref "MULTI") (pin "1") (pinfunction "A_1") (pintype "passive"))
      (node (ref "MULTI") (pin "CHASSIS2") (pinfunction "P$1_CHASSIS2") (pintype "passive"))
      (node (ref "OK") (pin "3") (pinfunction "P_3") (pintype "passive"))
      (node (ref "OK") (pin "4") (pinfunction "P_4") (pintype "passive"))
      (node (ref "Q7") (pin "E") (pinfunction "E_E") (pintype "passive"))
      (node (ref "Q8") (pin "E") (pinfunction "E_E") (pintype "passive"))
      (node (ref "R1") (pin "2") (pinfunction "2_2") (pintype "passive"))
      (node (ref "R2") (pin "2") (pinfunction "2_2") (pintype "passive"))
      (node (ref "R30") (pin "1") (pinfunction "1_1") (pintype "passive"))
      (node (ref "R30_2") (pin "1") (pinfunction "1_1") (pintype "passive"))
      (node (ref "R33") (pin "1") (pinfunction "1_1") (pintype "passive"))
      (node (ref "R35") (pin "1") (pinfunction "1_1") (pintype "passive"))
      (node (ref "R37") (pin "1") (pinfunction "1_1") (pintype "passive"))
      (node (ref "R4") (pin "1") (pinfunction "1_1") (pintype "passive"))
      (node (ref "R40") (pin "1") (pinfunction "1_1") (pintype "passive"))
      (node (ref "R44") (pin "1") (pinfunction "1_1") (pintype "passive"))
      (node (ref "R46") (pin "1") (pinfunction "1_1") (pintype "passive"))
      (node (ref "R48") (pin "1") (pinfunction "1_1") (pintype "passive"))
      (node (ref "R51") (pin "1") (pinfunction "1_1") (pintype "passive"))
      (node (ref "R6") (pin "1") (pinfunction "1_1") (pintype "passive"))
      (node (ref "RIGHT") (pin "3") (pinfunction "P_3") (pintype "passive"))
      (node (ref "RIGHT") (pin "4") (pinfunction "P_4") (pintype "passive"))
      (node (ref "U$1") (pin "10") (pinfunction "GND_10") (pintype "power_in"))
      (node (ref "U1") (pin "18") (pinfunction "GND1_18") (pintype "power_in"))
      (node (ref "U1") (pin "28") (pinfunction "GND_28") (pintype "power_in"))
      (node (ref "U1") (pin "39") (pinfunction "GND2_39") (pintype "power_in"))
      (node (ref "U1") (pin "6") (pinfunction "GND_6") (pintype "power_in"))
      (node (ref "U10") (pin "4") (pinfunction "V-_4") (pintype "power_in"))
      (node (ref "U3") (pin "7") (pinfunction "VSS_7") (pintype "power_in"))
      (node (ref "U8B") (pin "7") (pinfunction "GND_7") (pintype "power_in"))
    )
    (net (code "5") (name "Net-(BATA-S)") (class "Default")
      (node (ref "BAT") (pin "1") (pinfunction "S_1") (pintype "passive"))
      (node (ref "P_SWITCH") (pin "2") (pinfunction "2_2") (pintype "bidirectional"))
    )
    (net (code "6") (name "Net-(CHAN_A-Pad1)") (class "Default")
      (node (ref "CHAN_A") (pin "1") (pinfunction "1_1") (pintype "bidirectional"))
      (node (ref "TR1") (pin "3") (pinfunction "3_3") (pintype "passive"))
    )
    (net (code "7") (name "Net-(CHAN_A-Pad3)") (class "Default")
      (node (ref "CHAN_A") (pin "3") (pinfunction "3_3") (pintype "bidirectional"))
      (node (ref "TR1") (pin "1") (pinfunction "1_1") (pintype "passive"))
    )
    (net (code "8") (name "Net-(CHAN_B-Pad1)") (class "Default")
      (node (ref "CHAN_B") (pin "1") (pinfunction "1_1") (pintype "bidirectional"))
      (node (ref "TR2") (pin "3") (pinfunction "3_3") (pintype "passive"))
    )
    (net (code "9") (name "Net-(CHAN_B-Pad3)") (class "Default")
      (node (ref "CHAN_B") (pin "3") (pinfunction "3_3") (pintype "bidirectional"))
      (node (ref "TR2") (pin "1") (pinfunction "1_1") (pintype "passive"))
    )
    (net (code "10") (name "Net-(DC_IN-CENTER_PIN)") (class "Default")
      (node (ref "DC_IN") (pin "1") (pinfunction "CENTER_PIN_1") (pintype "bidirectional"))
      (node (ref "P_SWITCH") (pin "1") (pinfunction "1_1") (pintype "bidirectional"))
    )
    (net (code "11") (name "Net-(F1-Pad1)") (class "Default")
      (node (ref "F1") (pin "1") (pinfunction "1_1") (pintype "passive"))
      (node (ref "P_SWITCH") (pin "3") (pinfunction "3_3") (pintype "bidirectional"))
    )
    (net (code "12") (name "Net-(LCD1-A)") (class "Default")
      (node (ref "LCD1") (pin "15") (pinfunction "A_15") (pintype "input"))
      (node (ref "R12") (pin "1") (pinfunction "1_1") (pintype "passive"))
    )
    (net (code "13") (name "Net-(LCD1-K)") (class "Default")
      (node (ref "LCD1") (pin "16") (pinfunction "K_16") (pintype "input"))
      (node (ref "Q8") (pin "C") (pinfunction "C_C") (pintype "passive"))
    )
    (net (code "14") (name "Net-(LCD1-VO)") (class "Default")
      (node (ref "CONTR.") (pin "S") (pinfunction "S_S") (pintype "passive"))
      (node (ref "LCD1") (pin "3") (pinfunction "VO_3") (pintype "input"))
    )
    (net (code "15") (name "Net-(LED_CH_A-PadA)") (class "Default")
      (node (ref "LED_CH_A") (pin "A") (pinfunction "A_A") (pintype "passive"))
      (node (ref "R54") (pin "1") (pinfunction "1_1") (pintype "passive"))
    )
    (net (code "16") (name "Net-(LED_CH_B-PadA)") (class "Default")
      (node (ref "LED_CH_B") (pin "A") (pinfunction "A_A") (pintype "passive"))
      (node (ref "R53") (pin "1") (pinfunction "1_1") (pintype "passive"))
    )
    (net (code "17") (name "Net-(LED_POWER-PadA)") (class "Default")
      (node (ref "LED_POWER") (pin "A") (pinfunction "A_A") (pintype "passive"))
      (node (ref "R60") (pin "1") (pinfunction "1_1") (pintype "passive"))
    )
    (net (code "18") (name "Net-(MULTI-E)") (class "Default")
      (node (ref "MULTI") (pin "3") (pinfunction "E_3") (pintype "passive"))
      (node (ref "R7") (pin "1") (pinfunction "1_1") (pintype "passive"))
    )
    (net (code "19") (name "Net-(Q1-D-Pad2)") (class "Default")
      (node (ref "Q1") (pin "2") (pinfunction "D_2") (pintype "passive"))
      (node (ref "Q1") (pin "4") (pinfunction "D_4") (pintype "passive"))
      (node (ref "TR1") (pin "4") (pinfunction "4_4") (pintype "passive"))
    )
    (net (code "20") (name "Net-(Q1-G)") (class "Default")
      (node (ref "Q1") (pin "1") (pinfunction "G_1") (pintype "passive"))
      (node (ref "R38") (pin "2") (pinfunction "2_2") (pintype "passive"))
    )
    (net (code "21") (name "Net-(Q2-D-Pad2)") (class "Default")
      (node (ref "Q2") (pin "2") (pinfunction "D_2") (pintype "passive"))
      (node (ref "Q2") (pin "4") (pinfunction "D_4") (pintype "passive"))
      (node (ref "TR1") (pin "6") (pinfunction "6_6") (pintype "passive"))
    )
    (net (code "22") (name "Net-(Q2-G)") (class "Default")
      (node (ref "Q2") (pin "1") (pinfunction "G_1") (pintype "passive"))
      (node (ref "R41") (pin "2") (pinfunction "2_2") (pintype "passive"))
    )
    (net (code "23") (name "Net-(Q3-D-Pad2)") (class "Default")
      (node (ref "Q3") (pin "2") (pinfunction "D_2") (pintype "passive"))
      (node (ref "Q3") (pin "4") (pinfunction "D_4") (pintype "passive"))
      (node (ref "TR1") (pin "5") (pinfunction "5_5") (pintype "passive"))
    )
    (net (code "24") (name "Net-(Q3-G)") (class "Default")
      (node (ref "C39") (pin "1") (pinfunction "1_1") (pintype "passive"))
      (node (ref "Q3") (pin "1") (pinfunction "G_1") (pintype "passive"))
      (node (ref "R39") (pin "2") (pinfunction "2_2") (pintype "passive"))
    )
    (net (code "25") (name "Net-(Q4-D-Pad2)") (class "Default")
      (node (ref "Q4") (pin "2") (pinfunction "D_2") (pintype "passive"))
      (node (ref "Q4") (pin "4") (pinfunction "D_4") (pintype "passive"))
      (node (ref "TR2") (pin "4") (pinfunction "4_4") (pintype "passive"))
    )
    (net (code "26") (name "Net-(Q4-G)") (class "Default")
      (node (ref "Q4") (pin "1") (pinfunction "G_1") (pintype "passive"))
      (node (ref "R49") (pin "2") (pinfunction "2_2") (pintype "passive"))
    )
    (net (code "27") (name "Net-(Q5-D-Pad2)") (class "Default")
      (node (ref "Q5") (pin "2") (pinfunction "D_2") (pintype "passive"))
      (node (ref "Q5") (pin "4") (pinfunction "D_4") (pintype "passive"))
      (node (ref "TR2") (pin "6") (pinfunction "6_6") (pintype "passive"))
    )
    (net (code "28") (name "Net-(Q5-G)") (class "Default")
      (node (ref "Q5") (pin "1") (pinfunction "G_1") (pintype "passive"))
      (node (ref "R52") (pin "2") (pinfunction "2_2") (pintype "passive"))
    )
    (net (code "29") (name "Net-(Q6-D-Pad2)") (class "Default")
      (node (ref "Q6") (pin "2") (pinfunction "D_2") (pintype "passive"))
      (node (ref "Q6") (pin "4") (pinfunction "D_4") (pintype "passive"))
      (node (ref "TR2") (pin "5") (pinfunction "5_5") (pintype "passive"))
    )
    (net (code "30") (name "Net-(Q6-G)") (class "Default")
      (node (ref "C40") (pin "1") (pinfunction "1_1") (pintype "passive"))
      (node (ref "Q6") (pin "1") (pinfunction "G_1") (pintype "passive"))
      (node (ref "R50") (pin "2") (pinfunction "2_2") (pintype "passive"))
    )
    (net (code "31") (name "Net-(Q7-PadB)") (class "Default")
      (node (ref "Q7") (pin "B") (pinfunction "B_B") (pintype "passive"))
      (node (ref "R56") (pin "1") (pinfunction "1_1") (pintype "passive"))
    )
    (net (code "32") (name "Net-(Q7-PadC)") (class "Default")
      (node (ref "Q7") (pin "C") (pinfunction "C_C") (pintype "passive"))
      (node (ref "Q8") (pin "B") (pinfunction "B_B") (pintype "passive"))
      (node (ref "R57") (pin "2") (pinfunction "2_2") (pintype "passive"))
    )
    (net (code "33") (name "Net-(U$1-MODE_SYNC)") (class "Default")
      (node (ref "C12") (pin "1") (pinfunction "1_1") (pintype "passive"))
      (node (ref "U$1") (pin "11") (pinfunction "MODE_SYNC_11") (pintype "passive"))
      (node (ref "U$1") (pin "8") (pinfunction "VCC_8") (pintype "passive"))
    )
    (net (code "34") (name "Net-(U1-(ADC2)PA2)") (class "Default")
      (node (ref "R4") (pin "2") (pinfunction "2_2") (pintype "passive"))
      (node (ref "U1") (pin "35") (pinfunction "(ADC2)PA2_35") (pintype "bidirectional"))
    )
    (net (code "35") (name "Net-(U1-(ADC3)PA3)") (class "Default")
      (node (ref "R5") (pin "1") (pinfunction "1_1") (pintype "passive"))
      (node (ref "R6") (pin "2") (pinfunction "2_2") (pintype "passive"))
      (node (ref "U1") (pin "34") (pinfunction "(ADC3)PA3_34") (pintype "bidirectional"))
    )
    (net (code "36") (name "Net-(U1-(ADC6)PA6)") (class "Default")
      (node (ref "R2") (pin "1") (pinfunction "1_1") (pintype "passive"))
      (node (ref "U1") (pin "31") (pinfunction "(ADC6)PA6_31") (pintype "bidirectional"))
    )
    (net (code "37") (name "Net-(U1-(ADC7)PA7)") (class "Default")
      (node (ref "R1") (pin "1") (pinfunction "1_1") (pintype "passive"))
      (node (ref "U1") (pin "30") (pinfunction "(ADC7)PA7_30") (pintype "bidirectional"))
    )
    (net (code "38") (name "Net-(U1-(RXD)PD0)") (class "Default")
      (node (ref "U1") (pin "9") (pinfunction "(RXD)PD0_9") (pintype "bidirectional"))
      (node (ref "UART") (pin "2") (pinfunction "2_2") (pintype "passive"))
    )
    (net (code "39") (name "Net-(U1-(TXD)PD1)") (class "Default")
      (node (ref "U1") (pin "10") (pinfunction "(TXD)PD1_10") (pintype "bidirectional"))
      (node (ref "UART") (pin "1") (pinfunction "1_1") (pintype "passive"))
    )
    (net (code "40") (name "Net-(U1-XTAL1)") (class "Default")
      (node (ref "C16") (pin "1") (pinfunction "1_1") (pintype "passive"))
      (node (ref "U1") (pin "8") (pinfunction "XTAL1_8") (pintype "bidirectional"))
      (node (ref "Y1") (pin "2") (pinfunction "2_2") (pintype "passive"))
    )
    (net (code "41") (name "Net-(U1-XTAL2)") (class "Default")
      (node (ref "C15") (pin "1") (pinfunction "1_1") (pintype "passive"))
      (node (ref "U1") (pin "7") (pinfunction "XTAL2_7") (pintype "bidirectional"))
      (node (ref "Y1") (pin "1") (pinfunction "1_1") (pintype "passive"))
    )
    (net (code "42") (name "Net-(U3A-A)") (class "Default")
      (node (ref "C7") (pin "1") (pinfunction "1_1") (pintype "passive"))
      (node (ref "MENU") (pin "1") (pinfunction "S_1") (pintype "passive"))
      (node (ref "MENU") (pin "2") (pinfunction "S_2") (pintype "passive"))
      (node (ref "R11") (pin "2") (pinfunction "2_2") (pintype "passive"))
      (node (ref "U3") (pin "1") (pinfunction "A_1") (pintype "tri_state"))
    )
    (net (code "43") (name "Net-(U3B-A)") (class "Default")
      (node (ref "C5") (pin "1") (pinfunction "1_1") (pintype "passive"))
      (node (ref "R10") (pin "2") (pinfunction "2_2") (pintype "passive"))
      (node (ref "RIGHT") (pin "1") (pinfunction "S_1") (pintype "passive"))
      (node (ref "RIGHT") (pin "2") (pinfunction "S_2") (pintype "passive"))
      (node (ref "U3") (pin "4") (pinfunction "A_4") (pintype "tri_state"))
    )
    (net (code "44") (name "Net-(U3C-A)") (class "Default")
      (node (ref "C4") (pin "1") (pinfunction "1_1") (pintype "passive"))
      (node (ref "OK") (pin "1") (pinfunction "S_1") (pintype "passive"))
      (node (ref "OK") (pin "2") (pinfunction "S_2") (pintype "passive"))
      (node (ref "R9") (pin "2") (pinfunction "2_2") (pintype "passive"))
      (node (ref "U3") (pin "8") (pinfunction "A_8") (pintype "tri_state"))
    )
    (net (code "45") (name "Net-(U3D-A)") (class "Default")
      (node (ref "C3") (pin "1") (pinfunction "1_1") (pintype "passive"))
      (node (ref "LEFT") (pin "1") (pinfunction "S_1") (pintype "passive"))
      (node (ref "LEFT") (pin "2") (pinfunction "S_2") (pintype "passive"))
      (node (ref "R8") (pin "2") (pinfunction "2_2") (pintype "passive"))
      (node (ref "U3") (pin "11") (pinfunction "A_11") (pintype "tri_state"))
    )
    (net (code "46") (name "Net-(U8B-VOUT_A)") (class "Default")
      (node (ref "R42") (pin "1") (pinfunction "1_1") (pintype "passive"))
      (node (ref "U8B") (pin "8") (pinfunction "VOUT_A_8") (pintype "output"))
    )
    (net (code "47") (name "Net-(U8B-VOUT_B)") (class "Default")
      (node (ref "R31") (pin "1") (pinfunction "1_1") (pintype "passive"))
      (node (ref "U8B") (pin "5") (pinfunction "VOUT_B_5") (pintype "output"))
    )
    (net (code "48") (name "Net-(U10A-+IN)") (class "Default")
      (node (ref "R31") (pin "2") (pinfunction "2_2") (pintype "passive"))
      (node (ref "R32") (pin "1") (pinfunction "1_1") (pintype "passive"))
      (node (ref "R33") (pin "2") (pinfunction "2_2") (pintype "passive"))
      (node (ref "U10") (pin "3") (pinfunction "+IN_3") (pintype "input"))
    )
    (net (code "49") (name "Net-(U10A--IN)") (class "Default")
      (node (ref "R34") (pin "1") (pinfunction "1_1") (pintype "passive"))
      (node (ref "R35") (pin "2") (pinfunction "2_2") (pintype "passive"))
      (node (ref "R36") (pin "1") (pinfunction "1_1") (pintype "passive"))
      (node (ref "U10") (pin "2") (pinfunction "-IN_2") (pintype "input"))
    )
    (net (code "50") (name "Net-(U10A-OUT)") (class "Default")
      (node (ref "R36") (pin "2") (pinfunction "2_2") (pintype "passive"))
      (node (ref "R39") (pin "1") (pinfunction "1_1") (pintype "passive"))
      (node (ref "U10") (pin "1") (pinfunction "OUT_1") (pintype "output"))
    )
    (net (code "51") (name "Net-(U10B-+IN)") (class "Default")
      (node (ref "R42") (pin "2") (pinfunction "2_2") (pintype "passive"))
      (node (ref "R43") (pin "1") (pinfunction "1_1") (pintype "passive"))
      (node (ref "R44") (pin "2") (pinfunction "2_2") (pintype "passive"))
      (node (ref "U10") (pin "5") (pinfunction "+IN_5") (pintype "input"))
    )
    (net (code "52") (name "Net-(U10B--IN)") (class "Default")
      (node (ref "R45") (pin "1") (pinfunction "1_1") (pintype "passive"))
      (node (ref "R46") (pin "2") (pinfunction "2_2") (pintype "passive"))
      (node (ref "R47") (pin "1") (pinfunction "1_1") (pintype "passive"))
      (node (ref "U10") (pin "6") (pinfunction "-IN_6") (pintype "input"))
    )
    (net (code "53") (name "Net-(U10B-OUT)") (class "Default")
      (node (ref "R47") (pin "2") (pinfunction "2_2") (pintype "passive"))
      (node (ref "R50") (pin "1") (pinfunction "1_1") (pintype "passive"))
      (node (ref "U10") (pin "7") (pinfunction "OUT_7") (pintype "output"))
    )
    (net (code "54") (name "PA0") (class "Default")
      (node (ref "Q1") (pin "3") (pinfunction "S_3") (pintype "passive"))
      (node (ref "Q2") (pin "3") (pinfunction "S_3") (pintype "passive"))
      (node (ref "Q4") (pin "3") (pinfunction "S_3") (pintype "passive"))
      (node (ref "Q5") (pin "3") (pinfunction "S_3") (pintype "passive"))
      (node (ref "R30") (pin "2") (pinfunction "2_2") (pintype "passive"))
      (node (ref "R30_2") (pin "2") (pinfunction "2_2") (pintype "passive"))
      (node (ref "U1") (pin "37") (pinfunction "(ADC0)PA0_37") (pintype "bidirectional"))
    )
    (net (code "55") (name "PA1") (class "Default")
      (node (ref "MULTI") (pin "2") (pinfunction "S_2") (pintype "passive"))
      (node (ref "U1") (pin "36") (pinfunction "(ADC1)PA1_36") (pintype "bidirectional"))
    )
    (net (code "56") (name "PA4") (class "Default")
      (node (ref "LEVEL_A") (pin "2") (pinfunction "S_2") (pintype "passive"))
      (node (ref "U1") (pin "33") (pinfunction "(ADC4)PA4_33") (pintype "bidirectional"))
    )
    (net (code "57") (name "PA5") (class "Default")
      (node (ref "LEVEL_B") (pin "2") (pinfunction "S_2") (pintype "passive"))
      (node (ref "U1") (pin "32") (pinfunction "(ADC5)PA5_32") (pintype "bidirectional"))
    )
    (net (code "58") (name "PB0") (class "Default")
      (node (ref "R48") (pin "2") (pinfunction "2_2") (pintype "passive"))
      (node (ref "R49") (pin "1") (pinfunction "1_1") (pintype "passive"))
      (node (ref "U1") (pin "40") (pinfunction "(T0/XCK)PB0_40") (pintype "bidirectional"))
    )
    (net (code "59") (name "PB1") (class "Default")
      (node (ref "R51") (pin "2") (pinfunction "2_2") (pintype "passive"))
      (node (ref "R52") (pin "1") (pinfunction "1_1") (pintype "passive"))
      (node (ref "U1") (pin "41") (pinfunction "(T1)PB1_41") (pintype "bidirectional"))
    )
    (net (code "60") (name "PB2") (class "Default")
      (node (ref "R37") (pin "2") (pinfunction "2_2") (pintype "passive"))
      (node (ref "R38") (pin "1") (pinfunction "1_1") (pintype "passive"))
      (node (ref "U1") (pin "42") (pinfunction "(AIN0/INT2)PB2_42") (pintype "bidirectional"))
    )
    (net (code "61") (name "PB3") (class "Default")
      (node (ref "R40") (pin "2") (pinfunction "2_2") (pintype "passive"))
      (node (ref "R41") (pin "1") (pinfunction "1_1") (pintype "passive"))
      (node (ref "U1") (pin "43") (pinfunction "(AIN1/OC0)PB3_43") (pintype "bidirectional"))
    )
    (net (code "62") (name "PB5") (class "Default")
      (node (ref "ISP1") (pin "4") (pinfunction "MOSI_4") (pintype "output"))
      (node (ref "U1") (pin "1") (pinfunction "(MOSI)PB5_1") (pintype "bidirectional"))
      (node (ref "U8B") (pin "3") (pinfunction "D_IN_3") (pintype "input"))
    )
    (net (code "63") (name "PB6") (class "Default")
      (node (ref "ISP1") (pin "1") (pinfunction "MISO_1") (pintype "input"))
      (node (ref "U1") (pin "2") (pinfunction "(MISO)PB6_2") (pintype "bidirectional"))
    )
    (net (code "64") (name "PB7") (class "Default")
      (node (ref "ISP1") (pin "3") (pinfunction "SCK_3") (pintype "output"))
      (node (ref "U1") (pin "3") (pinfunction "(SCK)PB7_3") (pintype "bidirectional"))
      (node (ref "U8B") (pin "2") (pinfunction "SCK_2") (pintype "input"))
    )
    (net (code "65") (name "PC0") (class "Default")
      (node (ref "U1") (pin "19") (pinfunction "PC0(SCL)_19") (pintype "bidirectional"))
      (node (ref "U3") (pin "12") (pinfunction "C_12") (pintype "input"))
      (node (ref "U3") (pin "13") (pinfunction "C_13") (pintype "input"))
      (node (ref "U3") (pin "5") (pinfunction "C_5") (pintype "input"))
      (node (ref "U3") (pin "6") (pinfunction "C_6") (pintype "input"))
    )
    (net (code "66") (name "PC1") (class "Default")
      (node (ref "LCD1") (pin "5") (pinfunction "RW_5") (pintype "input"))
      (node (ref "U1") (pin "20") (pinfunction "PC1(SDA)_20") (pintype "bidirectional"))
    )
    (net (code "67") (name "PC2") (class "Default")
      (node (ref "LCD1") (pin "6") (pinfunction "E_6") (pintype "input"))
      (node (ref "U1") (pin "21") (pinfunction "(TCK)PC2_21") (pintype "bidirectional"))
    )
    (net (code "68") (name "PC3") (class "Default")
      (node (ref "LCD1") (pin "4") (pinfunction "RS_4") (pintype "input"))
      (node (ref "U1") (pin "22") (pinfunction "(TMS)PC3_22") (pintype "bidirectional"))
    )
    (net (code "69") (name "PC4") (class "Default")
      (node (ref "LCD1") (pin "11") (pinfunction "DB4_11") (pintype "bidirectional"))
      (node (ref "U1") (pin "23") (pinfunction "(TDO)PC4_23") (pintype "bidirectional"))
      (node (ref "U3") (pin "10") (pinfunction "B_10") (pintype "tri_state"))
    )
    (net (code "70") (name "PC5") (class "Default")
      (node (ref "LCD1") (pin "12") (pinfunction "DB5_12") (pintype "bidirectional"))
      (node (ref "U1") (pin "24") (pinfunction "(TDI)PC5_24") (pintype "bidirectional"))
      (node (ref "U3") (pin "9") (pinfunction "B_9") (pintype "tri_state"))
    )
    (net (code "71") (name "PC6") (class "Default")
      (node (ref "LCD1") (pin "13") (pinfunction "DB6_13") (pintype "bidirectional"))
      (node (ref "U1") (pin "25") (pinfunction "(TOSC1)PC6_25") (pintype "bidirectional"))
      (node (ref "U3") (pin "3") (pinfunction "B_3") (pintype "tri_state"))
    )
    (net (code "72") (name "PC7") (class "Default")
      (node (ref "LCD1") (pin "14") (pinfunction "DB7_14") (pintype "bidirectional"))
      (node (ref "U1") (pin "26") (pinfunction "(TOSC2)PC7_26") (pintype "bidirectional"))
      (node (ref "U3") (pin "2") (pinfunction "B_2") (pintype "tri_state"))
    )
    (net (code "73") (name "PD5") (class "Default")
      (node (ref "LED_CH_B") (pin "K") (pinfunction "C_K") (pintype "passive"))
      (node (ref "U1") (pin "14") (pinfunction "(OC1A)PD5_14") (pintype "bidirectional"))
    )
    (net (code "74") (name "PD6") (class "Default")
      (node (ref "LED_CH_A") (pin "K") (pinfunction "C_K") (pintype "passive"))
      (node (ref "U1") (pin "15") (pinfunction "(ICP)PD6_15") (pintype "bidirectional"))
    )
    (net (code "75") (name "PD7") (class "Default")
      (node (ref "R56") (pin "2") (pinfunction "2_2") (pintype "passive"))
      (node (ref "U1") (pin "16") (pinfunction "(OC2)PD7_16") (pintype "bidirectional"))
    )
    (net (code "76") (name "RESET") (class "Default")
      (node (ref "C8") (pin "1") (pinfunction "1_1") (pintype "passive"))
      (node (ref "ISP1") (pin "5") (pinfunction "RST_5") (pintype "output"))
      (node (ref "R3") (pin "1") (pinfunction "1_1") (pintype "passive"))
      (node (ref "U1") (pin "4") (pinfunction "RESET_4") (pintype "input"))
    )
    (net (code "77") (name "unconnected-(CHAN_A-Pad2)") (class "Default")
      (node (ref "CHAN_A") (pin "2") (pinfunction "2_2") (pintype "bidirectional"))
    )
    (net (code "78") (name "unconnected-(CHAN_B-Pad2)") (class "Default")
      (node (ref "CHAN_B") (pin "2") (pinfunction "2_2") (pintype "bidirectional"))
    )
    (net (code "79") (name "unconnected-(DC_IN-SLEEVE_SHUNT-Pad2)") (class "Default")
      (node (ref "DC_IN") (pin "2") (pinfunction "SLEEVE_SHUNT_2") (pintype "bidirectional"))
    )
    (net (code "80") (name "unconnected-(LCD1-DB0-Pad7)") (class "Default")
      (node (ref "LCD1") (pin "7") (pinfunction "DB0_7") (pintype "bidirectional"))
    )
    (net (code "81") (name "unconnected-(LCD1-DB1-Pad8)") (class "Default")
      (node (ref "LCD1") (pin "8") (pinfunction "DB1_8") (pintype "bidirectional"))
    )
    (net (code "82") (name "unconnected-(LCD1-DB2-Pad9)") (class "Default")
      (node (ref "LCD1") (pin "9") (pinfunction "DB2_9") (pintype "bidirectional"))
    )
    (net (code "83") (name "unconnected-(LCD1-DB3-Pad10)") (class "Default")
      (node (ref "LCD1") (pin "10") (pinfunction "DB3_10") (pintype "bidirectional"))
    )
    (net (code "84") (name "unconnected-(TR1-Pad2)") (class "Default")
      (node (ref "TR1") (pin "2") (pinfunction "2_2") (pintype "passive"))
    )
    (net (code "85") (name "unconnected-(TR2-Pad2)") (class "Default")
      (node (ref "TR2") (pin "2") (pinfunction "2_2") (pintype "passive"))
    )
    (net (code "86") (name "unconnected-(U$1-BOOT-Pad7)") (class "Default")
      (node (ref "U$1") (pin "7") (pinfunction "BOOT_7") (pintype "passive"))
    )
    (net (code "87") (name "unconnected-(U$1-PGOOD-Pad1)") (class "Default")
      (node (ref "U$1") (pin "1") (pinfunction "PGOOD_1") (pintype "open_collector"))
    )
    (net (code "88") (name "unconnected-(U$1-SW-Pad6)") (class "Default")
      (node (ref "U$1") (pin "6") (pinfunction "SW_6") (pintype "passive"))
    )
    (net (code "89") (name "unconnected-(U$1-SW_2-Pad5)") (class "Default")
      (node (ref "U$1") (pin "5") (pinfunction "SW_2_5") (pintype "passive"))
    )
    (net (code "90") (name "unconnected-(U1-(INT0)PD2-Pad11)") (class "Default")
      (node (ref "U1") (pin "11") (pinfunction "(INT0)PD2_11") (pintype "bidirectional"))
    )
    (net (code "91") (name "unconnected-(U1-(INT1)PD3-Pad12)") (class "Default")
      (node (ref "U1") (pin "12") (pinfunction "(INT1)PD3_12") (pintype "bidirectional"))
    )
    (net (code "92") (name "unconnected-(U1-(SS)PB4-Pad44)") (class "Default")
      (node (ref "U1") (pin "44") (pinfunction "(SS)PB4_44") (pintype "bidirectional"))
    )
    (net (code "93") (name "~{CS}") (class "Default")
      (node (ref "U1") (pin "13") (pinfunction "(OC1B)PD4_13") (pintype "bidirectional"))
      (node (ref "U8B") (pin "1") (pinfunction "CS/LD_1") (pintype "input"))
    )
  )
)
